# ESP12-breakout-smt-rev1.net
KiCad netlist of a schematic drawn in EAGLE
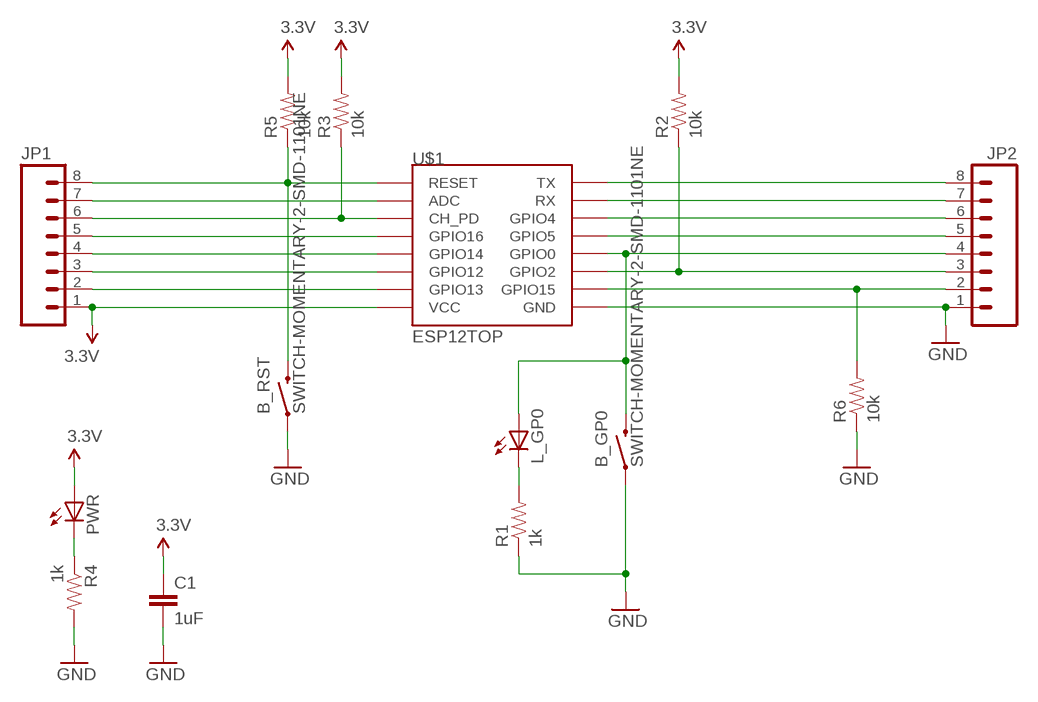
[diagram p0: schematic, sheet 1]

(export (version "E")
  (design (tool "Eeschema 10.0.6"))
  (components
    (comp (ref "B_GP0")
      (value "SWITCH-MOMENTARY-2-SMD-1101NE")
      (footprint "eagle-import:TACTILE-SWITCH-1101NE")
      (libsource (lib "eagle-import") (part "SWITCH-MOMENTARY-2-SMD-1101NE"))
    )
    (comp (ref "B_RST")
      (value "SWITCH-MOMENTARY-2-SMD-1101NE")
      (footprint "eagle-import:TACTILE-SWITCH-1101NE")
      (libsource (lib "eagle-import") (part "SWITCH-MOMENTARY-2-SMD-1101NE"))
    )
    (comp (ref "C1")
      (value "1uF")
      (footprint "eagle-import:0805")
      (libsource (lib "eagle-import") (part "CAP0805"))
    )
    (comp (ref "JP1")
      (value "M08")
      (footprint "eagle-import:1X08_PIN1_NO_SILK")
      (libsource (lib "eagle-import") (part "M08"))
    )
    (comp (ref "JP2")
      (value "M08")
      (footprint "eagle-import:1X08_PIN1_NO_SILK")
      (libsource (lib "eagle-import") (part "M08"))
    )
    (comp (ref "L_GP0")
      (value "LEDCHIPLED_0805")
      (footprint "eagle-import:CHIPLED_0805")
      (libsource (lib "eagle-import") (part "LEDCHIPLED_0805"))
    )
    (comp (ref "PWR")
      (value "LEDCHIPLED_0805")
      (footprint "eagle-import:CHIPLED_0805")
      (libsource (lib "eagle-import") (part "LEDCHIPLED_0805"))
    )
    (comp (ref "R1")
      (value "1k")
      (footprint "eagle-import:0603-RES")
      (libsource (lib "eagle-import") (part "RESISTOR0603"))
    )
    (comp (ref "R2")
      (value "10k")
      (footprint "eagle-import:0603-RES")
      (libsource (lib "eagle-import") (part "RESISTOR0603"))
    )
    (comp (ref "R3")
      (value "10k")
      (footprint "eagle-import:0603-RES")
      (libsource (lib "eagle-import") (part "RESISTOR0603"))
    )
    (comp (ref "R4")
      (value "1k")
      (footprint "eagle-import:0603-RES")
      (libsource (lib "eagle-import") (part "RESISTOR0603"))
    )
    (comp (ref "R5")
      (value "10k")
      (footprint "eagle-import:0603-RES")
      (libsource (lib "eagle-import") (part "RESISTOR0603"))
    )
    (comp (ref "R6")
      (value "10k")
      (footprint "eagle-import:0603-RES")
      (libsource (lib "eagle-import") (part "RESISTOR0603"))
    )
    (comp (ref "U$1")
      (value "ESP12TOP")
      (footprint "eagle-import:ESP12TOP")
      (libsource (lib "eagle-import") (part "ESP12TOP"))
    )
  )
  (nets
    (net (code "1") (name "3.3V") (class "Default")
      (node (ref "C1") (pin "1") (pinfunction "1_1") (pintype "passive"))
      (node (ref "JP1") (pin "1") (pinfunction "1_1") (pintype "passive"))
      (node (ref "PWR") (pin "A") (pinfunction "A_A") (pintype "passive"))
      (node (ref "R2") (pin "2") (pinfunction "2_2") (pintype "passive"))
      (node (ref "R3") (pin "2") (pinfunction "2_2") (pintype "passive"))
      (node (ref "R5") (pin "2") (pinfunction "2_2") (pintype "passive"))
      (node (ref "U$1") (pin "VCC") (pinfunction "VCC_VCC") (pintype "bidirectional"))
    )
    (net (code "2") (name "GND") (class "Default")
      (node (ref "B_GP0") (pin "1") (pinfunction "1_1") (pintype "passive"))
      (node (ref "B_RST") (pin "1") (pinfunction "1_1") (pintype "passive"))
      (node (ref "C1") (pin "2") (pinfunction "2_2") (pintype "passive"))
      (node (ref "JP2") (pin "1") (pinfunction "1_1") (pintype "passive"))
      (node (ref "R1") (pin "1") (pinfunction "1_1") (pintype "passive"))
      (node (ref "R4") (pin "2") (pinfunction "2_2") (pintype "passive"))
      (node (ref "R6") (pin "1") (pinfunction "1_1") (pintype "passive"))
      (node (ref "U$1") (pin "GND") (pinfunction "GND_GND") (pintype "bidirectional"))
    )
    (net (code "3") (name "Net-(B_GP0-Pad2)") (class "Default")
      (node (ref "B_GP0") (pin "2") (pinfunction "2_2") (pintype "passive"))
      (node (ref "JP2") (pin "4") (pinfunction "4_4") (pintype "passive"))
      (node (ref "L_GP0") (pin "A") (pinfunction "A_A") (pintype "passive"))
      (node (ref "U$1") (pin "GPIO0") (pinfunction "GPIO0_GPIO0") (pintype "bidirectional"))
    )
    (net (code "4") (name "Net-(B_RST-Pad2)") (class "Default")
      (node (ref "B_RST") (pin "2") (pinfunction "2_2") (pintype "passive"))
      (node (ref "JP1") (pin "8") (pinfunction "8_8") (pintype "passive"))
      (node (ref "R5") (pin "1") (pinfunction "1_1") (pintype "passive"))
      (node (ref "U$1") (pin "RESET") (pinfunction "RESET_RESET") (pintype "bidirectional"))
    )
    (net (code "5") (name "Net-(JP1-Pad2)") (class "Default")
      (node (ref "JP1") (pin "2") (pinfunction "2_2") (pintype "passive"))
      (node (ref "U$1") (pin "GPIO13") (pinfunction "GPIO13_GPIO13") (pintype "bidirectional"))
    )
    (net (code "6") (name "Net-(JP1-Pad3)") (class "Default")
      (node (ref "JP1") (pin "3") (pinfunction "3_3") (pintype "passive"))
      (node (ref "U$1") (pin "GPIO12") (pinfunction "GPIO12_GPIO12") (pintype "bidirectional"))
    )
    (net (code "7") (name "Net-(JP1-Pad4)") (class "Default")
      (node (ref "JP1") (pin "4") (pinfunction "4_4") (pintype "passive"))
      (node (ref "U$1") (pin "GPIO14") (pinfunction "GPIO14_GPIO14") (pintype "bidirectional"))
    )
    (net (code "8") (name "Net-(JP1-Pad5)") (class "Default")
      (node (ref "JP1") (pin "5") (pinfunction "5_5") (pintype "passive"))
      (node (ref "U$1") (pin "GPIO16") (pinfunction "GPIO16_GPIO16") (pintype "bidirectional"))
    )
    (net (code "9") (name "Net-(JP1-Pad6)") (class "Default")
      (node (ref "JP1") (pin "6") (pinfunction "6_6") (pintype "passive"))
      (node (ref "R3") (pin "1") (pinfunction "1_1") (pintype "passive"))
      (node (ref "U$1") (pin "CH_PD") (pinfunction "CH_PD_CH_PD") (pintype "bidirectional"))
    )
    (net (code "10") (name "Net-(JP1-Pad7)") (class "Default")
      (node (ref "JP1") (pin "7") (pinfunction "7_7") (pintype "passive"))
      (node (ref "U$1") (pin "ADC") (pinfunction "ADC_ADC") (pintype "bidirectional"))
    )
    (net (code "11") (name "Net-(JP2-Pad2)") (class "Default")
      (node (ref "JP2") (pin "2") (pinfunction "2_2") (pintype "passive"))
      (node (ref "R6") (pin "2") (pinfunction "2_2") (pintype "passive"))
      (node (ref "U$1") (pin "GPIO15") (pinfunction "GPIO15_GPIO15") (pintype "bidirectional"))
    )
    (net (code "12") (name "Net-(JP2-Pad3)") (class "Default")
      (node (ref "JP2") (pin "3") (pinfunction "3_3") (pintype "passive"))
      (node (ref "R2") (pin "1") (pinfunction "1_1") (pintype "passive"))
      (node (ref "U$1") (pin "GPIO2") (pinfunction "GPIO2_GPIO2") (pintype "bidirectional"))
    )
    (net (code "13") (name "Net-(JP2-Pad5)") (class "Default")
      (node (ref "JP2") (pin "5") (pinfunction "5_5") (pintype "passive"))
      (node (ref "U$1") (pin "GPIO5") (pinfunction "GPIO5_GPIO5") (pintype "bidirectional"))
    )
    (net (code "14") (name "Net-(JP2-Pad6)") (class "Default")
      (node (ref "JP2") (pin "6") (pinfunction "6_6") (pintype "passive"))
      (node (ref "U$1") (pin "GPIO4") (pinfunction "GPIO4_GPIO4") (pintype "bidirectional"))
    )
    (net (code "15") (name "Net-(L_GP0-PadC)") (class "Default")
      (node (ref "L_GP0") (pin "C") (pinfunction "C_C") (pintype "passive"))
      (node (ref "R1") (pin "2") (pinfunction "2_2") (pintype "passive"))
    )
    (net (code "16") (name "Net-(PWR-PadC)") (class "Default")
      (node (ref "PWR") (pin "C") (pinfunction "C_C") (pintype "passive"))
      (node (ref "R4") (pin "1") (pinfunction "1_1") (pintype "passive"))
    )
    (net (code "17") (name "Net-(U$1-RX)") (class "Default")
      (node (ref "JP2") (pin "7") (pinfunction "7_7") (pintype "passive"))
      (node (ref "U$1") (pin "RXD") (pinfunction "RX_RXD") (pintype "bidirectional"))
    )
    (net (code "18") (name "Net-(U$1-TX)") (class "Default")
      (node (ref "JP2") (pin "8") (pinfunction "8_8") (pintype "passive"))
      (node (ref "U$1") (pin "TXD") (pinfunction "TX_TXD") (pintype "bidirectional"))
    )
  )
)
